# 485_tranceiver.net
KiCad netlist of a schematic drawn in Altium Designer
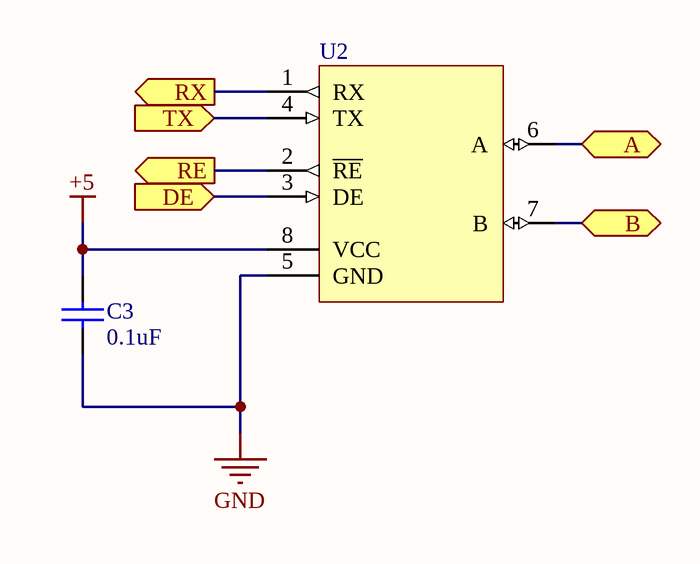
[diagram p0: 485_tranceiver.SchDoc]

(export (version "E")
  (design (tool "Eeschema 10.0.6"))
  (components
    (comp (ref "C3")
      (value "0.1uF")
      (footprint "CAPC1608X90X35NL20T15")
      (description "CAP CER 0.1UF 50V 10% X7R 0603")
      (libsource (lib "CommunityVault") (part "CMP-120344-2"))
    )
    (comp (ref "U2")
      (value "STMicroelectronics ST3485ECDR")
      (footprint "PCB-lmrwxhl2h1q3b67kej26-1")
      (description "ST3485E Series 3.3 V ±15 kV ESD Protected RS-485/RS-422 Transceiver - SOIC-8")
      (fields (field (name "MANUFACTURER PART NUMBER") "ST3485ECDR"))
      (libsource (lib "CommunityVault") (part "CMP-4f81868cdec19046-4"))
    )
  )
  (nets
    (net (code "1") (name "+5") (class "Default")
      (node (ref "C3") (pin "2") (pinfunction "2_2") (pintype "passive"))
      (node (ref "U2") (pin "8") (pinfunction "VCC_8") (pintype "power_in"))
    )
    (net (code "2") (name "/A") (class "Default")
      (node (ref "U2") (pin "6") (pinfunction "A_6") (pintype "bidirectional"))
    )
    (net (code "3") (name "/B") (class "Default")
      (node (ref "U2") (pin "7") (pinfunction "B_7") (pintype "bidirectional"))
    )
    (net (code "4") (name "/DE") (class "Default")
      (node (ref "U2") (pin "3") (pinfunction "DE_3") (pintype "input"))
    )
    (net (code "5") (name "/RE") (class "Default")
      (node (ref "U2") (pin "2") (pinfunction "~{RE}_2") (pintype "output"))
    )
    (net (code "6") (name "/RX") (class "Default")
      (node (ref "U2") (pin "1") (pinfunction "RX_1") (pintype "output"))
    )
    (net (code "7") (name "/TX") (class "Default")
      (node (ref "U2") (pin "4") (pinfunction "TX_4") (pintype "input"))
    )
    (net (code "8") (name "GND") (class "Default")
      (node (ref "C3") (pin "1") (pinfunction "1_1") (pintype "passive"))
      (node (ref "U2") (pin "5") (pinfunction "GND_5") (pintype "power_in"))
    )
  )
)
